# GSMPart.net
KiCad netlist of a schematic drawn in Altium Designer
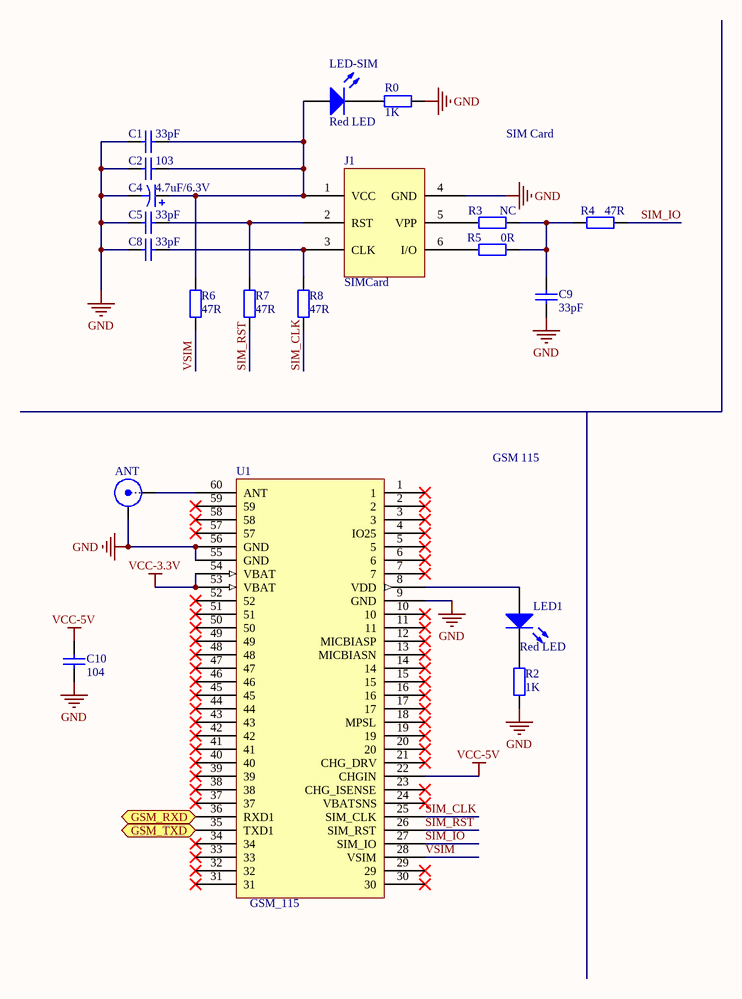
[diagram p0: GSMPart.SchDoc]

(export (version "E")
  (design (tool "Eeschema 10.0.6"))
  (components
    (comp (ref "ANT")
      (value "SMB")
      (footprint "SMB_V-RJ45")
      (description "SMB Straight Connector")
      (fields (field (name "PUBLISHER") "Altium Limited"))
      (libsource (lib "Miscellaneous Connectors") (part "SMB"))
    )
    (comp (ref "C1")
      (value "33pF")
      (footprint "1608[0603]")
      (description "Capacitor")
      (fields (field (name "Comment") "Cap") (field (name "PUBLISHER") "Altium Limited"))
      (libsource (lib "common") (part "Cap"))
    )
    (comp (ref "C2")
      (value "103")
      (footprint "1608[0603]")
      (description "Capacitor")
      (fields (field (name "Comment") "Cap") (field (name "PUBLISHER") "Altium Limited"))
      (libsource (lib "common") (part "Cap"))
    )
    (comp (ref "C4")
      (value "4.7uF/6.3V")
      (footprint "Standard:B")
      (description "Polarized Capacitor (Axial)")
      (fields (field (name "Comment") "CAP POL") (field (name "PUBLISHER") "Altium Limited"))
      (libsource (lib "common") (part "CAP POL"))
    )
    (comp (ref "C5")
      (value "33pF")
      (footprint "1608[0603]")
      (description "Capacitor")
      (fields (field (name "Comment") "Cap") (field (name "PUBLISHER") "Altium Limited"))
      (libsource (lib "common") (part "Cap"))
    )
    (comp (ref "C8")
      (value "33pF")
      (footprint "1608[0603]")
      (description "Capacitor")
      (fields (field (name "Comment") "Cap") (field (name "PUBLISHER") "Altium Limited"))
      (libsource (lib "common") (part "Cap"))
    )
    (comp (ref "C9")
      (value "33pF")
      (footprint "1608[0603]")
      (description "Capacitor")
      (fields (field (name "Comment") "Cap") (field (name "PUBLISHER") "Altium Limited"))
      (libsource (lib "common") (part "Cap"))
    )
    (comp (ref "C10")
      (value "104")
      (footprint "1608[0603]")
      (description "Capacitor")
      (fields (field (name "Comment") "Cap") (field (name "PUBLISHER") "Altium Limited"))
      (libsource (lib "common") (part "Cap"))
    )
    (comp (ref "J1")
      (value "SIMCard")
      (footprint "PCB_SIM")
      (description "Sim Card")
      (libsource (lib "GSM") (part "SIMCard"))
    )
    (comp (ref "LED-SIM")
      (value "Red LED")
      (footprint "2012[0805] - POL")
      (libsource (lib "common") (part "LED"))
    )
    (comp (ref "LED1")
      (value "Red LED")
      (footprint "2012[0805] - POL")
      (libsource (lib "common") (part "LED"))
    )
    (comp (ref "R0")
      (value "1K")
      (footprint "1608[0603]")
      (description "Resistor")
      (fields (field (name "Comment") "RES") (field (name "PUBLISHER") "Altium Limited"))
      (libsource (lib "") (part "RES_2"))
    )
    (comp (ref "R2")
      (value "1K")
      (footprint "1608[0603]")
      (description "Resistor")
      (fields (field (name "Comment") "RES") (field (name "PUBLISHER") "Altium Limited"))
      (libsource (lib "common") (part "RES"))
    )
    (comp (ref "R3")
      (value "NC")
      (footprint "1608[0603]")
      (description "Resistor")
      (fields (field (name "Comment") "RES") (field (name "PUBLISHER") "Altium Limited"))
      (libsource (lib "") (part "RES_1"))
    )
    (comp (ref "R4")
      (value "47R")
      (footprint "1608[0603]")
      (description "Resistor")
      (fields (field (name "Comment") "RES") (field (name "PUBLISHER") "Altium Limited"))
      (libsource (lib "") (part "RES_1"))
    )
    (comp (ref "R5")
      (value "0R")
      (footprint "1608[0603]")
      (description "Resistor")
      (fields (field (name "Comment") "RES") (field (name "PUBLISHER") "Altium Limited"))
      (libsource (lib "") (part "RES_1"))
    )
    (comp (ref "R6")
      (value "47R")
      (footprint "1608[0603]")
      (description "Resistor")
      (fields (field (name "Comment") "RES") (field (name "PUBLISHER") "Altium Limited"))
      (libsource (lib "common") (part "RES"))
    )
    (comp (ref "R7")
      (value "47R")
      (footprint "1608[0603]")
      (description "Resistor")
      (fields (field (name "Comment") "RES") (field (name "PUBLISHER") "Altium Limited"))
      (libsource (lib "common") (part "RES"))
    )
    (comp (ref "R8")
      (value "47R")
      (footprint "1608[0603]")
      (description "Resistor")
      (fields (field (name "Comment") "RES") (field (name "PUBLISHER") "Altium Limited"))
      (libsource (lib "common") (part "RES"))
    )
    (comp (ref "U1") (value "GSM_115") (libsource (lib "GSM") (part "GSM115")))
  )
  (nets
    (net (code "1") (name "/GSM_RXD") (class "Default")
      (node (ref "U1") (pin "36") (pinfunction "RXD1_36") (pintype "passive"))
    )
    (net (code "2") (name "/GSM_TXD") (class "Default")
      (node (ref "U1") (pin "35") (pinfunction "TXD1_35") (pintype "passive"))
    )
    (net (code "3") (name "/SIM_CLK") (class "Default")
      (node (ref "R8") (pin "1") (pinfunction "1_1") (pintype "passive"))
      (node (ref "U1") (pin "25") (pinfunction "SIM_CLK_25") (pintype "passive"))
    )
    (net (code "4") (name "/SIM_IO") (class "Default")
      (node (ref "R4") (pin "2") (pinfunction "2_2") (pintype "passive"))
      (node (ref "U1") (pin "27") (pinfunction "SIM_IO_27") (pintype "passive"))
    )
    (net (code "5") (name "/SIM_RST") (class "Default")
      (node (ref "R7") (pin "1") (pinfunction "1_1") (pintype "passive"))
      (node (ref "U1") (pin "26") (pinfunction "SIM_RST_26") (pintype "passive"))
    )
    (net (code "6") (name "/VSIM") (class "Default")
      (node (ref "R6") (pin "1") (pinfunction "1_1") (pintype "passive"))
      (node (ref "U1") (pin "28") (pinfunction "VSIM_28") (pintype "passive"))
    )
    (net (code "7") (name "GND") (class "Default")
      (node (ref "ANT") (pin "2") (pinfunction "Y_2") (pintype "passive"))
      (node (ref "C1") (pin "1") (pinfunction "1_1") (pintype "passive"))
      (node (ref "C10") (pin "1") (pinfunction "1_1") (pintype "passive"))
      (node (ref "C2") (pin "1") (pinfunction "1_1") (pintype "passive"))
      (node (ref "C4") (pin "2") (pinfunction "2_2") (pintype "passive"))
      (node (ref "C5") (pin "1") (pinfunction "1_1") (pintype "passive"))
      (node (ref "C8") (pin "1") (pinfunction "1_1") (pintype "passive"))
      (node (ref "C9") (pin "1") (pinfunction "1_1") (pintype "passive"))
      (node (ref "J1") (pin "4") (pinfunction "GND_4") (pintype "passive"))
      (node (ref "R0") (pin "1") (pinfunction "1_1") (pintype "passive"))
      (node (ref "R2") (pin "1") (pinfunction "1_1") (pintype "passive"))
      (node (ref "U1") (pin "55") (pinfunction "GND_55") (pintype "passive"))
      (node (ref "U1") (pin "56") (pinfunction "GND_56") (pintype "passive"))
      (node (ref "U1") (pin "9") (pinfunction "GND_9") (pintype "passive"))
    )
    (net (code "8") (name "Net-(ANT-X)") (class "Default")
      (node (ref "ANT") (pin "1") (pinfunction "X_1") (pintype "passive"))
      (node (ref "U1") (pin "60") (pinfunction "ANT_60") (pintype "passive"))
    )
    (net (code "9") (name "Net-(C9-Pad2)") (class "Default")
      (node (ref "C9") (pin "2") (pinfunction "2_2") (pintype "passive"))
      (node (ref "R3") (pin "2") (pinfunction "2_2") (pintype "passive"))
      (node (ref "R4") (pin "1") (pinfunction "1_1") (pintype "passive"))
      (node (ref "R5") (pin "2") (pinfunction "2_2") (pintype "passive"))
    )
    (net (code "10") (name "Net-(J1-CLK)") (class "Default")
      (node (ref "C8") (pin "2") (pinfunction "2_2") (pintype "passive"))
      (node (ref "J1") (pin "3") (pinfunction "CLK_3") (pintype "passive"))
      (node (ref "R8") (pin "2") (pinfunction "2_2") (pintype "passive"))
    )
    (net (code "11") (name "Net-(J1-I{slash}O)") (class "Default")
      (node (ref "J1") (pin "6") (pinfunction "I/O_6") (pintype "passive"))
      (node (ref "R5") (pin "1") (pinfunction "1_1") (pintype "passive"))
    )
    (net (code "12") (name "Net-(J1-RST)") (class "Default")
      (node (ref "C5") (pin "2") (pinfunction "2_2") (pintype "passive"))
      (node (ref "J1") (pin "2") (pinfunction "RST_2") (pintype "passive"))
      (node (ref "R7") (pin "2") (pinfunction "2_2") (pintype "passive"))
    )
    (net (code "13") (name "Net-(J1-VCC)") (class "Default")
      (node (ref "C1") (pin "2") (pinfunction "2_2") (pintype "passive"))
      (node (ref "C2") (pin "2") (pinfunction "2_2") (pintype "passive"))
      (node (ref "C4") (pin "1") (pinfunction "1_1") (pintype "passive"))
      (node (ref "J1") (pin "1") (pinfunction "VCC_1") (pintype "passive"))
      (node (ref "LED-SIM") (pin "1") (pinfunction "A_1") (pintype "passive"))
      (node (ref "R6") (pin "2") (pinfunction "2_2") (pintype "passive"))
    )
    (net (code "14") (name "Net-(J1-VPP)") (class "Default")
      (node (ref "J1") (pin "5") (pinfunction "VPP_5") (pintype "passive"))
      (node (ref "R3") (pin "1") (pinfunction "1_1") (pintype "passive"))
    )
    (net (code "15") (name "Net-(LED-SIM-K)") (class "Default")
      (node (ref "LED-SIM") (pin "2") (pinfunction "K_2") (pintype "passive"))
      (node (ref "R0") (pin "2") (pinfunction "2_2") (pintype "passive"))
    )
    (net (code "16") (name "Net-(LED1-A)") (class "Default")
      (node (ref "LED1") (pin "1") (pinfunction "A_1") (pintype "passive"))
      (node (ref "U1") (pin "8") (pinfunction "VDD_8") (pintype "output"))
    )
    (net (code "17") (name "Net-(LED1-K)") (class "Default")
      (node (ref "LED1") (pin "2") (pinfunction "K_2") (pintype "passive"))
      (node (ref "R2") (pin "2") (pinfunction "2_2") (pintype "passive"))
    )
    (net (code "18") (name "VCC-3.3V") (class "Default")
      (node (ref "U1") (pin "53") (pinfunction "VBAT_53") (pintype "input"))
      (node (ref "U1") (pin "54") (pinfunction "VBAT_54") (pintype "input"))
    )
    (net (code "19") (name "VCC-5V") (class "Default")
      (node (ref "C10") (pin "2") (pinfunction "2_2") (pintype "passive"))
      (node (ref "U1") (pin "22") (pinfunction "CHGIN_22") (pintype "passive"))
    )
    (net (code "20") (name "unconnected-(U1-CHG_DRV-Pad21)") (class "Default")
      (node (ref "U1") (pin "21") (pinfunction "CHG_DRV_21") (pintype "passive+no_connect"))
    )
    (net (code "21") (name "unconnected-(U1-CHG_ISENSE-Pad23)") (class "Default")
      (node (ref "U1") (pin "23") (pinfunction "CHG_ISENSE_23") (pintype "passive+no_connect"))
    )
    (net (code "22") (name "unconnected-(U1-IO25-Pad4)") (class "Default")
      (node (ref "U1") (pin "4") (pinfunction "IO25_4") (pintype "passive+no_connect"))
    )
    (net (code "23") (name "unconnected-(U1-MICBIASN-Pad13)") (class "Default")
      (node (ref "U1") (pin "13") (pinfunction "MICBIASN_13") (pintype "passive+no_connect"))
    )
    (net (code "24") (name "unconnected-(U1-MICBIASP-Pad12)") (class "Default")
      (node (ref "U1") (pin "12") (pinfunction "MICBIASP_12") (pintype "passive+no_connect"))
    )
    (net (code "25") (name "unconnected-(U1-MPSL-Pad18)") (class "Default")
      (node (ref "U1") (pin "18") (pinfunction "MPSL_18") (pintype "passive+no_connect"))
    )
    (net (code "26") (name "unconnected-(U1-Pad1)") (class "Default")
      (node (ref "U1") (pin "1") (pinfunction "1_1") (pintype "passive+no_connect"))
    )
    (net (code "27") (name "unconnected-(U1-Pad2)") (class "Default")
      (node (ref "U1") (pin "2") (pinfunction "2_2") (pintype "passive+no_connect"))
    )
    (net (code "28") (name "unconnected-(U1-Pad3)") (class "Default")
      (node (ref "U1") (pin "3") (pinfunction "3_3") (pintype "passive+no_connect"))
    )
    (net (code "29") (name "unconnected-(U1-Pad5)") (class "Default")
      (node (ref "U1") (pin "5") (pinfunction "5_5") (pintype "passive+no_connect"))
    )
    (net (code "30") (name "unconnected-(U1-Pad6)") (class "Default")
      (node (ref "U1") (pin "6") (pinfunction "6_6") (pintype "passive+no_connect"))
    )
    (net (code "31") (name "unconnected-(U1-Pad7)") (class "Default")
      (node (ref "U1") (pin "7") (pinfunction "7_7") (pintype "passive+no_connect"))
    )
    (net (code "32") (name "unconnected-(U1-Pad10)") (class "Default")
      (node (ref "U1") (pin "10") (pinfunction "10_10") (pintype "passive+no_connect"))
    )
    (net (code "33") (name "unconnected-(U1-Pad11)") (class "Default")
      (node (ref "U1") (pin "11") (pinfunction "11_11") (pintype "passive+no_connect"))
    )
    (net (code "34") (name "unconnected-(U1-Pad14)") (class "Default")
      (node (ref "U1") (pin "14") (pinfunction "14_14") (pintype "passive+no_connect"))
    )
    (net (code "35") (name "unconnected-(U1-Pad15)") (class "Default")
      (node (ref "U1") (pin "15") (pinfunction "15_15") (pintype "passive+no_connect"))
    )
    (net (code "36") (name "unconnected-(U1-Pad16)") (class "Default")
      (node (ref "U1") (pin "16") (pinfunction "16_16") (pintype "passive+no_connect"))
    )
    (net (code "37") (name "unconnected-(U1-Pad17)") (class "Default")
      (node (ref "U1") (pin "17") (pinfunction "17_17") (pintype "passive+no_connect"))
    )
    (net (code "38") (name "unconnected-(U1-Pad19)") (class "Default")
      (node (ref "U1") (pin "19") (pinfunction "19_19") (pintype "passive+no_connect"))
    )
    (net (code "39") (name "unconnected-(U1-Pad20)") (class "Default")
      (node (ref "U1") (pin "20") (pinfunction "20_20") (pintype "passive+no_connect"))
    )
    (net (code "40") (name "unconnected-(U1-Pad29)") (class "Default")
      (node (ref "U1") (pin "29") (pinfunction "29_29") (pintype "passive+no_connect"))
    )
    (net (code "41") (name "unconnected-(U1-Pad30)") (class "Default")
      (node (ref "U1") (pin "30") (pinfunction "30_30") (pintype "passive+no_connect"))
    )
    (net (code "42") (name "unconnected-(U1-Pad31)") (class "Default")
      (node (ref "U1") (pin "31") (pinfunction "31_31") (pintype "passive+no_connect"))
    )
    (net (code "43") (name "unconnected-(U1-Pad32)") (class "Default")
      (node (ref "U1") (pin "32") (pinfunction "32_32") (pintype "passive+no_connect"))
    )
    (net (code "44") (name "unconnected-(U1-Pad33)") (class "Default")
      (node (ref "U1") (pin "33") (pinfunction "33_33") (pintype "passive+no_connect"))
    )
    (net (code "45") (name "unconnected-(U1-Pad34)") (class "Default")
      (node (ref "U1") (pin "34") (pinfunction "34_34") (pintype "passive+no_connect"))
    )
    (net (code "46") (name "unconnected-(U1-Pad37)") (class "Default")
      (node (ref "U1") (pin "37") (pinfunction "37_37") (pintype "passive+no_connect"))
    )
    (net (code "47") (name "unconnected-(U1-Pad38)") (class "Default")
      (node (ref "U1") (pin "38") (pinfunction "38_38") (pintype "passive+no_connect"))
    )
    (net (code "48") (name "unconnected-(U1-Pad39)") (class "Default")
      (node (ref "U1") (pin "39") (pinfunction "39_39") (pintype "passive+no_connect"))
    )
    (net (code "49") (name "unconnected-(U1-Pad40)") (class "Default")
      (node (ref "U1") (pin "40") (pinfunction "40_40") (pintype "passive+no_connect"))
    )
    (net (code "50") (name "unconnected-(U1-Pad41)") (class "Default")
      (node (ref "U1") (pin "41") (pinfunction "41_41") (pintype "passive+no_connect"))
    )
    (net (code "51") (name "unconnected-(U1-Pad42)") (class "Default")
      (node (ref "U1") (pin "42") (pinfunction "42_42") (pintype "passive+no_connect"))
    )
    (net (code "52") (name "unconnected-(U1-Pad43)") (class "Default")
      (node (ref "U1") (pin "43") (pinfunction "43_43") (pintype "passive+no_connect"))
    )
    (net (code "53") (name "unconnected-(U1-Pad44)") (class "Default")
      (node (ref "U1") (pin "44") (pinfunction "44_44") (pintype "passive+no_connect"))
    )
    (net (code "54") (name "unconnected-(U1-Pad45)") (class "Default")
      (node (ref "U1") (pin "45") (pinfunction "45_45") (pintype "passive+no_connect"))
    )
    (net (code "55") (name "unconnected-(U1-Pad46)") (class "Default")
      (node (ref "U1") (pin "46") (pinfunction "46_46") (pintype "passive+no_connect"))
    )
    (net (code "56") (name "unconnected-(U1-Pad47)") (class "Default")
      (node (ref "U1") (pin "47") (pinfunction "47_47") (pintype "passive+no_connect"))
    )
    (net (code "57") (name "unconnected-(U1-Pad48)") (class "Default")
      (node (ref "U1") (pin "48") (pinfunction "48_48") (pintype "passive+no_connect"))
    )
    (net (code "58") (name "unconnected-(U1-Pad49)") (class "Default")
      (node (ref "U1") (pin "49") (pinfunction "49_49") (pintype "passive+no_connect"))
    )
    (net (code "59") (name "unconnected-(U1-Pad50)") (class "Default")
      (node (ref "U1") (pin "50") (pinfunction "50_50") (pintype "passive+no_connect"))
    )
    (net (code "60") (name "unconnected-(U1-Pad51)") (class "Default")
      (node (ref "U1") (pin "51") (pinfunction "51_51") (pintype "passive+no_connect"))
    )
    (net (code "61") (name "unconnected-(U1-Pad52)") (class "Default")
      (node (ref "U1") (pin "52") (pinfunction "52_52") (pintype "passive+no_connect"))
    )
    (net (code "62") (name "unconnected-(U1-Pad57)") (class "Default")
      (node (ref "U1") (pin "57") (pinfunction "57_57") (pintype "passive+no_connect"))
    )
    (net (code "63") (name "unconnected-(U1-Pad58)") (class "Default")
      (node (ref "U1") (pin "58") (pinfunction "58_58") (pintype "passive+no_connect"))
    )
    (net (code "64") (name "unconnected-(U1-Pad59)") (class "Default")
      (node (ref "U1") (pin "59") (pinfunction "59_59") (pintype "passive+no_connect"))
    )
    (net (code "65") (name "unconnected-(U1-VBATSNS-Pad24)") (class "Default")
      (node (ref "U1") (pin "24") (pinfunction "VBATSNS_24") (pintype "passive+no_connect"))
    )
  )
)
